# Res.net
KiCad netlist of a schematic drawn in Altium Designer
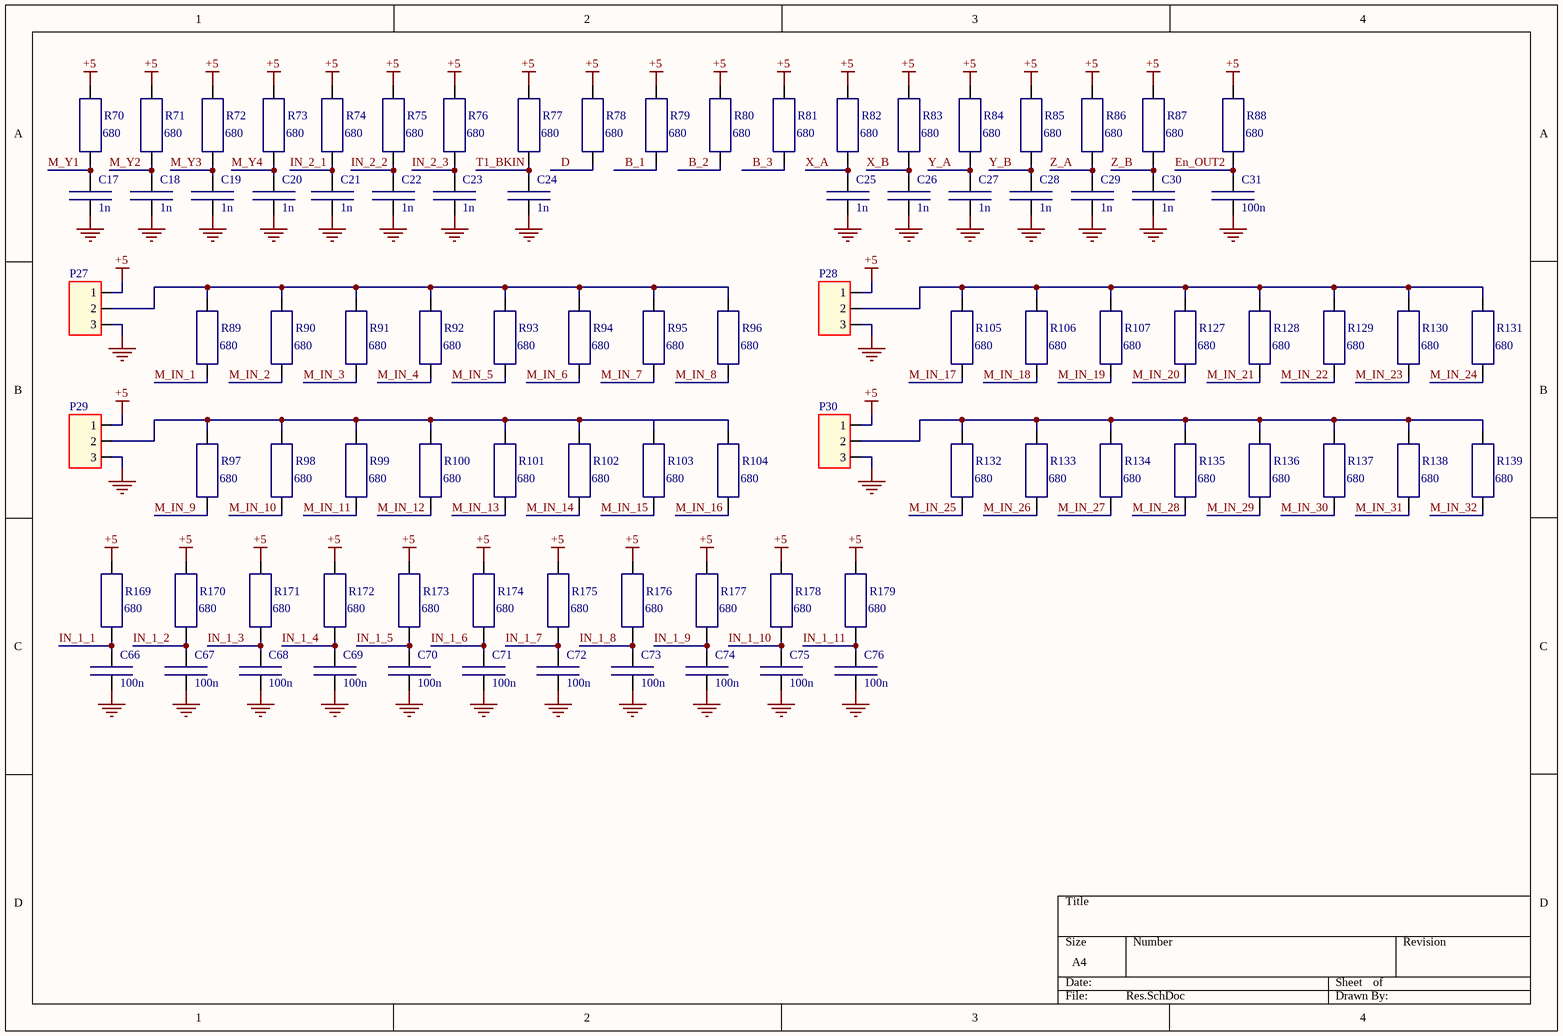
[diagram p0: Res.SchDoc]

(export (version "E")
  (design (tool "Eeschema 10.0.6"))
  (components
    (comp (ref "C17") (value "1n") (footprint "C0805") (libsource (lib "Library") (part "C0805")))
    (comp (ref "C18") (value "1n") (footprint "C0805") (libsource (lib "Library") (part "C0805")))
    (comp (ref "C19") (value "1n") (footprint "C0805") (libsource (lib "Library") (part "C0805")))
    (comp (ref "C20") (value "1n") (footprint "C0805") (libsource (lib "Library") (part "C0805")))
    (comp (ref "C21") (value "1n") (footprint "C0805") (libsource (lib "Library") (part "C0805")))
    (comp (ref "C22") (value "1n") (footprint "C0805") (libsource (lib "Library") (part "C0805")))
    (comp (ref "C23") (value "1n") (footprint "C0805") (libsource (lib "Library") (part "C0805")))
    (comp (ref "C24") (value "1n") (footprint "C0805") (libsource (lib "Library") (part "C0805")))
    (comp (ref "C25") (value "1n") (footprint "C0805") (libsource (lib "Library") (part "C0805")))
    (comp (ref "C26") (value "1n") (footprint "C0805") (libsource (lib "Library") (part "C0805")))
    (comp (ref "C27") (value "1n") (footprint "C0805") (libsource (lib "Library") (part "C0805")))
    (comp (ref "C28") (value "1n") (footprint "C0805") (libsource (lib "Library") (part "C0805")))
    (comp (ref "C29") (value "1n") (footprint "C0805") (libsource (lib "Library") (part "C0805")))
    (comp (ref "C30") (value "1n") (footprint "C0805") (libsource (lib "Library") (part "C0805")))
    (comp (ref "C31") (value "100n") (footprint "C0805") (libsource (lib "Library") (part "C0805")))
    (comp (ref "C66") (value "100n") (footprint "C0805") (libsource (lib "Library") (part "C0805")))
    (comp (ref "C67") (value "100n") (footprint "C0805") (libsource (lib "Library") (part "C0805")))
    (comp (ref "C68") (value "100n") (footprint "C0805") (libsource (lib "Library") (part "C0805")))
    (comp (ref "C69") (value "100n") (footprint "C0805") (libsource (lib "Library") (part "C0805")))
    (comp (ref "C70") (value "100n") (footprint "C0805") (libsource (lib "Library") (part "C0805")))
    (comp (ref "C71") (value "100n") (footprint "C0805") (libsource (lib "Library") (part "C0805")))
    (comp (ref "C72") (value "100n") (footprint "C0805") (libsource (lib "Library") (part "C0805")))
    (comp (ref "C73") (value "100n") (footprint "C0805") (libsource (lib "Library") (part "C0805")))
    (comp (ref "C74") (value "100n") (footprint "C0805") (libsource (lib "Library") (part "C0805")))
    (comp (ref "C75") (value "100n") (footprint "C0805") (libsource (lib "Library") (part "C0805")))
    (comp (ref "C76") (value "100n") (footprint "C0805") (libsource (lib "Library") (part "C0805")))
    (comp (ref "P27") (value "Con_3") (footprint "CON_3") (libsource (lib "Library") (part "Con_3")))
    (comp (ref "P28") (value "Con_3") (footprint "CON_3") (libsource (lib "Library") (part "Con_3")))
    (comp (ref "P29") (value "Con_3") (footprint "CON_3") (libsource (lib "Library") (part "Con_3")))
    (comp (ref "P30") (value "Con_3") (footprint "CON_3") (libsource (lib "Library") (part "Con_3")))
    (comp (ref "R70") (value "680") (footprint "R0805") (libsource (lib "Library") (part "R0805")))
    (comp (ref "R71") (value "680") (footprint "R0805") (libsource (lib "Library") (part "R0805")))
    (comp (ref "R72") (value "680") (footprint "R0805") (libsource (lib "Library") (part "R0805")))
    (comp (ref "R73") (value "680") (footprint "R0805") (libsource (lib "Library") (part "R0805")))
    (comp (ref "R74") (value "680") (footprint "R0805") (libsource (lib "Library") (part "R0805")))
    (comp (ref "R75") (value "680") (footprint "R0805") (libsource (lib "Library") (part "R0805")))
    (comp (ref "R76") (value "680") (footprint "R0805") (libsource (lib "Library") (part "R0805")))
    (comp (ref "R77") (value "680") (footprint "R0805") (libsource (lib "Library") (part "R0805")))
    (comp (ref "R78") (value "680") (footprint "R0805") (libsource (lib "Library") (part "R0805")))
    (comp (ref "R79") (value "680") (footprint "R0805") (libsource (lib "Library") (part "R0805")))
    (comp (ref "R80") (value "680") (footprint "R0805") (libsource (lib "Library") (part "R0805")))
    (comp (ref "R81") (value "680") (footprint "R0805") (libsource (lib "Library") (part "R0805")))
    (comp (ref "R82") (value "680") (footprint "R0805") (libsource (lib "Library") (part "R0805")))
    (comp (ref "R83") (value "680") (footprint "R0805") (libsource (lib "Library") (part "R0805")))
    (comp (ref "R84") (value "680") (footprint "R0805") (libsource (lib "Library") (part "R0805")))
    (comp (ref "R85") (value "680") (footprint "R0805") (libsource (lib "Library") (part "R0805")))
    (comp (ref "R86") (value "680") (footprint "R0805") (libsource (lib "Library") (part "R0805")))
    (comp (ref "R87") (value "680") (footprint "R0805") (libsource (lib "Library") (part "R0805")))
    (comp (ref "R88") (value "680") (footprint "R0805") (libsource (lib "Library") (part "R0805")))
    (comp (ref "R89") (value "680") (footprint "R0805") (libsource (lib "Library") (part "R0805")))
    (comp (ref "R90") (value "680") (footprint "R0805") (libsource (lib "Library") (part "R0805")))
    (comp (ref "R91") (value "680") (footprint "R0805") (libsource (lib "Library") (part "R0805")))
    (comp (ref "R92") (value "680") (footprint "R0805") (libsource (lib "Library") (part "R0805")))
    (comp (ref "R93") (value "680") (footprint "R0805") (libsource (lib "Library") (part "R0805")))
    (comp (ref "R94") (value "680") (footprint "R0805") (libsource (lib "Library") (part "R0805")))
    (comp (ref "R95") (value "680") (footprint "R0805") (libsource (lib "Library") (part "R0805")))
    (comp (ref "R96") (value "680") (footprint "R0805") (libsource (lib "Library") (part "R0805")))
    (comp (ref "R97") (value "680") (footprint "R0805") (libsource (lib "Library") (part "R0805")))
    (comp (ref "R98") (value "680") (footprint "R0805") (libsource (lib "Library") (part "R0805")))
    (comp (ref "R99") (value "680") (footprint "R0805") (libsource (lib "Library") (part "R0805")))
    (comp (ref "R100") (value "680") (footprint "R0805") (libsource (lib "Library") (part "R0805")))
    (comp (ref "R101") (value "680") (footprint "R0805") (libsource (lib "Library") (part "R0805")))
    (comp (ref "R102") (value "680") (footprint "R0805") (libsource (lib "Library") (part "R0805")))
    (comp (ref "R103") (value "680") (footprint "R0805") (libsource (lib "Library") (part "R0805")))
    (comp (ref "R104") (value "680") (footprint "R0805") (libsource (lib "Library") (part "R0805")))
    (comp (ref "R105") (value "680") (footprint "R0805") (libsource (lib "Library") (part "R0805")))
    (comp (ref "R106") (value "680") (footprint "R0805") (libsource (lib "Library") (part "R0805")))
    (comp (ref "R107") (value "680") (footprint "R0805") (libsource (lib "Library") (part "R0805")))
    (comp (ref "R127") (value "680") (footprint "R0805") (libsource (lib "Library") (part "R0805")))
    (comp (ref "R128") (value "680") (footprint "R0805") (libsource (lib "Library") (part "R0805")))
    (comp (ref "R129") (value "680") (footprint "R0805") (libsource (lib "Library") (part "R0805")))
    (comp (ref "R130") (value "680") (footprint "R0805") (libsource (lib "Library") (part "R0805")))
    (comp (ref "R131") (value "680") (footprint "R0805") (libsource (lib "Library") (part "R0805")))
    (comp (ref "R132") (value "680") (footprint "R0805") (libsource (lib "Library") (part "R0805")))
    (comp (ref "R133") (value "680") (footprint "R0805") (libsource (lib "Library") (part "R0805")))
    (comp (ref "R134") (value "680") (footprint "R0805") (libsource (lib "Library") (part "R0805")))
    (comp (ref "R135") (value "680") (footprint "R0805") (libsource (lib "Library") (part "R0805")))
    (comp (ref "R136") (value "680") (footprint "R0805") (libsource (lib "Library") (part "R0805")))
    (comp (ref "R137") (value "680") (footprint "R0805") (libsource (lib "Library") (part "R0805")))
    (comp (ref "R138") (value "680") (footprint "R0805") (libsource (lib "Library") (part "R0805")))
    (comp (ref "R139") (value "680") (footprint "R0805") (libsource (lib "Library") (part "R0805")))
    (comp (ref "R169") (value "680") (footprint "R0805") (libsource (lib "Library") (part "R0805")))
    (comp (ref "R170") (value "680") (footprint "R0805") (libsource (lib "Library") (part "R0805")))
    (comp (ref "R171") (value "680") (footprint "R0805") (libsource (lib "Library") (part "R0805")))
    (comp (ref "R172") (value "680") (footprint "R0805") (libsource (lib "Library") (part "R0805")))
    (comp (ref "R173") (value "680") (footprint "R0805") (libsource (lib "Library") (part "R0805")))
    (comp (ref "R174") (value "680") (footprint "R0805") (libsource (lib "Library") (part "R0805")))
    (comp (ref "R175") (value "680") (footprint "R0805") (libsource (lib "Library") (part "R0805")))
    (comp (ref "R176") (value "680") (footprint "R0805") (libsource (lib "Library") (part "R0805")))
    (comp (ref "R177") (value "680") (footprint "R0805") (libsource (lib "Library") (part "R0805")))
    (comp (ref "R178") (value "680") (footprint "R0805") (libsource (lib "Library") (part "R0805")))
    (comp (ref "R179") (value "680") (footprint "R0805") (libsource (lib "Library") (part "R0805")))
  )
  (nets
    (net (code "1") (name "+5") (class "Default")
      (node (ref "P27") (pin "1") (pinfunction "1_1") (pintype "passive"))
      (node (ref "P28") (pin "1") (pinfunction "1_1") (pintype "passive"))
      (node (ref "P29") (pin "1") (pinfunction "1_1") (pintype "passive"))
      (node (ref "P30") (pin "1") (pinfunction "1_1") (pintype "passive"))
      (node (ref "R169") (pin "2") (pinfunction "2_2") (pintype "passive"))
      (node (ref "R170") (pin "2") (pinfunction "2_2") (pintype "passive"))
      (node (ref "R171") (pin "2") (pinfunction "2_2") (pintype "passive"))
      (node (ref "R172") (pin "2") (pinfunction "2_2") (pintype "passive"))
      (node (ref "R173") (pin "2") (pinfunction "2_2") (pintype "passive"))
      (node (ref "R174") (pin "2") (pinfunction "2_2") (pintype "passive"))
      (node (ref "R175") (pin "2") (pinfunction "2_2") (pintype "passive"))
      (node (ref "R176") (pin "2") (pinfunction "2_2") (pintype "passive"))
      (node (ref "R177") (pin "2") (pinfunction "2_2") (pintype "passive"))
      (node (ref "R178") (pin "2") (pinfunction "2_2") (pintype "passive"))
      (node (ref "R179") (pin "2") (pinfunction "2_2") (pintype "passive"))
      (node (ref "R70") (pin "2") (pinfunction "2_2") (pintype "passive"))
      (node (ref "R71") (pin "2") (pinfunction "2_2") (pintype "passive"))
      (node (ref "R72") (pin "2") (pinfunction "2_2") (pintype "passive"))
      (node (ref "R73") (pin "2") (pinfunction "2_2") (pintype "passive"))
      (node (ref "R74") (pin "2") (pinfunction "2_2") (pintype "passive"))
      (node (ref "R75") (pin "2") (pinfunction "2_2") (pintype "passive"))
      (node (ref "R76") (pin "2") (pinfunction "2_2") (pintype "passive"))
      (node (ref "R77") (pin "2") (pinfunction "2_2") (pintype "passive"))
      (node (ref "R78") (pin "2") (pinfunction "2_2") (pintype "passive"))
      (node (ref "R79") (pin "2") (pinfunction "2_2") (pintype "passive"))
      (node (ref "R80") (pin "2") (pinfunction "2_2") (pintype "passive"))
      (node (ref "R81") (pin "2") (pinfunction "2_2") (pintype "passive"))
      (node (ref "R82") (pin "2") (pinfunction "2_2") (pintype "passive"))
      (node (ref "R83") (pin "2") (pinfunction "2_2") (pintype "passive"))
      (node (ref "R84") (pin "2") (pinfunction "2_2") (pintype "passive"))
      (node (ref "R85") (pin "2") (pinfunction "2_2") (pintype "passive"))
      (node (ref "R86") (pin "2") (pinfunction "2_2") (pintype "passive"))
      (node (ref "R87") (pin "2") (pinfunction "2_2") (pintype "passive"))
      (node (ref "R88") (pin "2") (pinfunction "2_2") (pintype "passive"))
    )
    (net (code "2") (name "/B_1") (class "Default")
      (node (ref "R79") (pin "1") (pinfunction "1_1") (pintype "passive"))
    )
    (net (code "3") (name "/B_2") (class "Default")
      (node (ref "R80") (pin "1") (pinfunction "1_1") (pintype "passive"))
    )
    (net (code "4") (name "/B_3") (class "Default")
      (node (ref "R81") (pin "1") (pinfunction "1_1") (pintype "passive"))
    )
    (net (code "5") (name "/D") (class "Default")
      (node (ref "R78") (pin "1") (pinfunction "1_1") (pintype "passive"))
    )
    (net (code "6") (name "/En_OUT2") (class "Default")
      (node (ref "C31") (pin "1") (pinfunction "1_1") (pintype "passive"))
      (node (ref "R88") (pin "1") (pinfunction "1_1") (pintype "passive"))
    )
    (net (code "7") (name "/IN_1_1") (class "Default")
      (node (ref "C66") (pin "1") (pinfunction "1_1") (pintype "passive"))
      (node (ref "R169") (pin "1") (pinfunction "1_1") (pintype "passive"))
    )
    (net (code "8") (name "/IN_1_2") (class "Default")
      (node (ref "C67") (pin "1") (pinfunction "1_1") (pintype "passive"))
      (node (ref "R170") (pin "1") (pinfunction "1_1") (pintype "passive"))
    )
    (net (code "9") (name "/IN_1_3") (class "Default")
      (node (ref "C68") (pin "1") (pinfunction "1_1") (pintype "passive"))
      (node (ref "R171") (pin "1") (pinfunction "1_1") (pintype "passive"))
    )
    (net (code "10") (name "/IN_1_4") (class "Default")
      (node (ref "C69") (pin "1") (pinfunction "1_1") (pintype "passive"))
      (node (ref "R172") (pin "1") (pinfunction "1_1") (pintype "passive"))
    )
    (net (code "11") (name "/IN_1_5") (class "Default")
      (node (ref "C70") (pin "1") (pinfunction "1_1") (pintype "passive"))
      (node (ref "R173") (pin "1") (pinfunction "1_1") (pintype "passive"))
    )
    (net (code "12") (name "/IN_1_6") (class "Default")
      (node (ref "C71") (pin "1") (pinfunction "1_1") (pintype "passive"))
      (node (ref "R174") (pin "1") (pinfunction "1_1") (pintype "passive"))
    )
    (net (code "13") (name "/IN_1_7") (class "Default")
      (node (ref "C72") (pin "1") (pinfunction "1_1") (pintype "passive"))
      (node (ref "R175") (pin "1") (pinfunction "1_1") (pintype "passive"))
    )
    (net (code "14") (name "/IN_1_8") (class "Default")
      (node (ref "C73") (pin "1") (pinfunction "1_1") (pintype "passive"))
      (node (ref "R176") (pin "1") (pinfunction "1_1") (pintype "passive"))
    )
    (net (code "15") (name "/IN_1_9") (class "Default")
      (node (ref "C74") (pin "1") (pinfunction "1_1") (pintype "passive"))
      (node (ref "R177") (pin "1") (pinfunction "1_1") (pintype "passive"))
    )
    (net (code "16") (name "/IN_1_10") (class "Default")
      (node (ref "C75") (pin "1") (pinfunction "1_1") (pintype "passive"))
      (node (ref "R178") (pin "1") (pinfunction "1_1") (pintype "passive"))
    )
    (net (code "17") (name "/IN_1_11") (class "Default")
      (node (ref "C76") (pin "1") (pinfunction "1_1") (pintype "passive"))
      (node (ref "R179") (pin "1") (pinfunction "1_1") (pintype "passive"))
    )
    (net (code "18") (name "/IN_2_1") (class "Default")
      (node (ref "C21") (pin "1") (pinfunction "1_1") (pintype "passive"))
      (node (ref "R74") (pin "1") (pinfunction "1_1") (pintype "passive"))
    )
    (net (code "19") (name "/IN_2_2") (class "Default")
      (node (ref "C22") (pin "1") (pinfunction "1_1") (pintype "passive"))
      (node (ref "R75") (pin "1") (pinfunction "1_1") (pintype "passive"))
    )
    (net (code "20") (name "/IN_2_3") (class "Default")
      (node (ref "C23") (pin "1") (pinfunction "1_1") (pintype "passive"))
      (node (ref "R76") (pin "1") (pinfunction "1_1") (pintype "passive"))
    )
    (net (code "21") (name "/M_IN_1") (class "Default")
      (node (ref "R89") (pin "1") (pinfunction "1_1") (pintype "passive"))
    )
    (net (code "22") (name "/M_IN_2") (class "Default")
      (node (ref "R90") (pin "1") (pinfunction "1_1") (pintype "passive"))
    )
    (net (code "23") (name "/M_IN_3") (class "Default")
      (node (ref "R91") (pin "1") (pinfunction "1_1") (pintype "passive"))
    )
    (net (code "24") (name "/M_IN_4") (class "Default")
      (node (ref "R92") (pin "1") (pinfunction "1_1") (pintype "passive"))
    )
    (net (code "25") (name "/M_IN_5") (class "Default")
      (node (ref "R93") (pin "1") (pinfunction "1_1") (pintype "passive"))
    )
    (net (code "26") (name "/M_IN_6") (class "Default")
      (node (ref "R94") (pin "1") (pinfunction "1_1") (pintype "passive"))
    )
    (net (code "27") (name "/M_IN_7") (class "Default")
      (node (ref "R95") (pin "1") (pinfunction "1_1") (pintype "passive"))
    )
    (net (code "28") (name "/M_IN_8") (class "Default")
      (node (ref "R96") (pin "1") (pinfunction "1_1") (pintype "passive"))
    )
    (net (code "29") (name "/M_IN_9") (class "Default")
      (node (ref "R97") (pin "1") (pinfunction "1_1") (pintype "passive"))
    )
    (net (code "30") (name "/M_IN_10") (class "Default")
      (node (ref "R98") (pin "1") (pinfunction "1_1") (pintype "passive"))
    )
    (net (code "31") (name "/M_IN_11") (class "Default")
      (node (ref "R99") (pin "1") (pinfunction "1_1") (pintype "passive"))
    )
    (net (code "32") (name "/M_IN_12") (class "Default")
      (node (ref "R100") (pin "1") (pinfunction "1_1") (pintype "passive"))
    )
    (net (code "33") (name "/M_IN_13") (class "Default")
      (node (ref "R101") (pin "1") (pinfunction "1_1") (pintype "passive"))
    )
    (net (code "34") (name "/M_IN_14") (class "Default")
      (node (ref "R102") (pin "1") (pinfunction "1_1") (pintype "passive"))
    )
    (net (code "35") (name "/M_IN_15") (class "Default")
      (node (ref "R103") (pin "1") (pinfunction "1_1") (pintype "passive"))
    )
    (net (code "36") (name "/M_IN_16") (class "Default")
      (node (ref "R104") (pin "1") (pinfunction "1_1") (pintype "passive"))
    )
    (net (code "37") (name "/M_IN_17") (class "Default")
      (node (ref "R105") (pin "1") (pinfunction "1_1") (pintype "passive"))
    )
    (net (code "38") (name "/M_IN_18") (class "Default")
      (node (ref "R106") (pin "1") (pinfunction "1_1") (pintype "passive"))
    )
    (net (code "39") (name "/M_IN_19") (class "Default")
      (node (ref "R107") (pin "1") (pinfunction "1_1") (pintype "passive"))
    )
    (net (code "40") (name "/M_IN_20") (class "Default")
      (node (ref "R127") (pin "1") (pinfunction "1_1") (pintype "passive"))
    )
    (net (code "41") (name "/M_IN_21") (class "Default")
      (node (ref "R128") (pin "1") (pinfunction "1_1") (pintype "passive"))
    )
    (net (code "42") (name "/M_IN_22") (class "Default")
      (node (ref "R129") (pin "1") (pinfunction "1_1") (pintype "passive"))
    )
    (net (code "43") (name "/M_IN_23") (class "Default")
      (node (ref "R130") (pin "1") (pinfunction "1_1") (pintype "passive"))
    )
    (net (code "44") (name "/M_IN_24") (class "Default")
      (node (ref "R131") (pin "1") (pinfunction "1_1") (pintype "passive"))
    )
    (net (code "45") (name "/M_IN_25") (class "Default")
      (node (ref "R132") (pin "1") (pinfunction "1_1") (pintype "passive"))
    )
    (net (code "46") (name "/M_IN_26") (class "Default")
      (node (ref "R133") (pin "1") (pinfunction "1_1") (pintype "passive"))
    )
    (net (code "47") (name "/M_IN_27") (class "Default")
      (node (ref "R134") (pin "1") (pinfunction "1_1") (pintype "passive"))
    )
    (net (code "48") (name "/M_IN_28") (class "Default")
      (node (ref "R135") (pin "1") (pinfunction "1_1") (pintype "passive"))
    )
    (net (code "49") (name "/M_IN_29") (class "Default")
      (node (ref "R136") (pin "1") (pinfunction "1_1") (pintype "passive"))
    )
    (net (code "50") (name "/M_IN_30") (class "Default")
      (node (ref "R137") (pin "1") (pinfunction "1_1") (pintype "passive"))
    )
    (net (code "51") (name "/M_IN_31") (class "Default")
      (node (ref "R138") (pin "1") (pinfunction "1_1") (pintype "passive"))
    )
    (net (code "52") (name "/M_IN_32") (class "Default")
      (node (ref "R139") (pin "1") (pinfunction "1_1") (pintype "passive"))
    )
    (net (code "53") (name "/M_Y1") (class "Default")
      (node (ref "C17") (pin "1") (pinfunction "1_1") (pintype "passive"))
      (node (ref "R70") (pin "1") (pinfunction "1_1") (pintype "passive"))
    )
    (net (code "54") (name "/M_Y2") (class "Default")
      (node (ref "C18") (pin "1") (pinfunction "1_1") (pintype "passive"))
      (node (ref "R71") (pin "1") (pinfunction "1_1") (pintype "passive"))
    )
    (net (code "55") (name "/M_Y3") (class "Default")
      (node (ref "C19") (pin "1") (pinfunction "1_1") (pintype "passive"))
      (node (ref "R72") (pin "1") (pinfunction "1_1") (pintype "passive"))
    )
    (net (code "56") (name "/M_Y4") (class "Default")
      (node (ref "C20") (pin "1") (pinfunction "1_1") (pintype "passive"))
      (node (ref "R73") (pin "1") (pinfunction "1_1") (pintype "passive"))
    )
    (net (code "57") (name "/T1_BKIN") (class "Default")
      (node (ref "C24") (pin "1") (pinfunction "1_1") (pintype "passive"))
      (node (ref "R77") (pin "1") (pinfunction "1_1") (pintype "passive"))
    )
    (net (code "58") (name "/X_A") (class "Default")
      (node (ref "C25") (pin "1") (pinfunction "1_1") (pintype "passive"))
      (node (ref "R82") (pin "1") (pinfunction "1_1") (pintype "passive"))
    )
    (net (code "59") (name "/X_B") (class "Default")
      (node (ref "C26") (pin "1") (pinfunction "1_1") (pintype "passive"))
      (node (ref "R83") (pin "1") (pinfunction "1_1") (pintype "passive"))
    )
    (net (code "60") (name "/Y_A") (class "Default")
      (node (ref "C27") (pin "1") (pinfunction "1_1") (pintype "passive"))
      (node (ref "R84") (pin "1") (pinfunction "1_1") (pintype "passive"))
    )
    (net (code "61") (name "/Y_B") (class "Default")
      (node (ref "C28") (pin "1") (pinfunction "1_1") (pintype "passive"))
      (node (ref "R85") (pin "1") (pinfunction "1_1") (pintype "passive"))
    )
    (net (code "62") (name "/Z_A") (class "Default")
      (node (ref "C29") (pin "1") (pinfunction "1_1") (pintype "passive"))
      (node (ref "R86") (pin "1") (pinfunction "1_1") (pintype "passive"))
    )
    (net (code "63") (name "/Z_B") (class "Default")
      (node (ref "C30") (pin "1") (pinfunction "1_1") (pintype "passive"))
      (node (ref "R87") (pin "1") (pinfunction "1_1") (pintype "passive"))
    )
    (net (code "64") (name "GND") (class "Default")
      (node (ref "C17") (pin "2") (pinfunction "2_2") (pintype "passive"))
      (node (ref "C18") (pin "2") (pinfunction "2_2") (pintype "passive"))
      (node (ref "C19") (pin "2") (pinfunction "2_2") (pintype "passive"))
      (node (ref "C20") (pin "2") (pinfunction "2_2") (pintype "passive"))
      (node (ref "C21") (pin "2") (pinfunction "2_2") (pintype "passive"))
      (node (ref "C22") (pin "2") (pinfunction "2_2") (pintype "passive"))
      (node (ref "C23") (pin "2") (pinfunction "2_2") (pintype "passive"))
      (node (ref "C24") (pin "2") (pinfunction "2_2") (pintype "passive"))
      (node (ref "C25") (pin "2") (pinfunction "2_2") (pintype "passive"))
      (node (ref "C26") (pin "2") (pinfunction "2_2") (pintype "passive"))
      (node (ref "C27") (pin "2") (pinfunction "2_2") (pintype "passive"))
      (node (ref "C28") (pin "2") (pinfunction "2_2") (pintype "passive"))
      (node (ref "C29") (pin "2") (pinfunction "2_2") (pintype "passive"))
      (node (ref "C30") (pin "2") (pinfunction "2_2") (pintype "passive"))
      (node (ref "C31") (pin "2") (pinfunction "2_2") (pintype "passive"))
      (node (ref "C66") (pin "2") (pinfunction "2_2") (pintype "passive"))
      (node (ref "C67") (pin "2") (pinfunction "2_2") (pintype "passive"))
      (node (ref "C68") (pin "2") (pinfunction "2_2") (pintype "passive"))
      (node (ref "C69") (pin "2") (pinfunction "2_2") (pintype "passive"))
      (node (ref "C70") (pin "2") (pinfunction "2_2") (pintype "passive"))
      (node (ref "C71") (pin "2") (pinfunction "2_2") (pintype "passive"))
      (node (ref "C72") (pin "2") (pinfunction "2_2") (pintype "passive"))
      (node (ref "C73") (pin "2") (pinfunction "2_2") (pintype "passive"))
      (node (ref "C74") (pin "2") (pinfunction "2_2") (pintype "passive"))
      (node (ref "C75") (pin "2") (pinfunction "2_2") (pintype "passive"))
      (node (ref "C76") (pin "2") (pinfunction "2_2") (pintype "passive"))
      (node (ref "P27") (pin "3") (pinfunction "3_3") (pintype "passive"))
      (node (ref "P28") (pin "3") (pinfunction "3_3") (pintype "passive"))
      (node (ref "P29") (pin "3") (pinfunction "3_3") (pintype "passive"))
      (node (ref "P30") (pin "3") (pinfunction "3_3") (pintype "passive"))
    )
    (net (code "65") (name "Net-(P27-Pad2)") (class "Default")
      (node (ref "P27") (pin "2") (pinfunction "2_2") (pintype "passive"))
      (node (ref "R89") (pin "2") (pinfunction "2_2") (pintype "passive"))
      (node (ref "R90") (pin "2") (pinfunction "2_2") (pintype "passive"))
      (node (ref "R91") (pin "2") (pinfunction "2_2") (pintype "passive"))
      (node (ref "R92") (pin "2") (pinfunction "2_2") (pintype "passive"))
      (node (ref "R93") (pin "2") (pinfunction "2_2") (pintype "passive"))
      (node (ref "R94") (pin "2") (pinfunction "2_2") (pintype "passive"))
      (node (ref "R95") (pin "2") (pinfunction "2_2") (pintype "passive"))
      (node (ref "R96") (pin "2") (pinfunction "2_2") (pintype "passive"))
    )
    (net (code "66") (name "Net-(P28-Pad2)") (class "Default")
      (node (ref "P28") (pin "2") (pinfunction "2_2") (pintype "passive"))
      (node (ref "R105") (pin "2") (pinfunction "2_2") (pintype "passive"))
      (node (ref "R106") (pin "2") (pinfunction "2_2") (pintype "passive"))
      (node (ref "R107") (pin "2") (pinfunction "2_2") (pintype "passive"))
      (node (ref "R127") (pin "2") (pinfunction "2_2") (pintype "passive"))
      (node (ref "R128") (pin "2") (pinfunction "2_2") (pintype "passive"))
      (node (ref "R129") (pin "2") (pinfunction "2_2") (pintype "passive"))
      (node (ref "R130") (pin "2") (pinfunction "2_2") (pintype "passive"))
      (node (ref "R131") (pin "2") (pinfunction "2_2") (pintype "passive"))
    )
    (net (code "67") (name "Net-(P29-Pad2)") (class "Default")
      (node (ref "P29") (pin "2") (pinfunction "2_2") (pintype "passive"))
      (node (ref "R100") (pin "2") (pinfunction "2_2") (pintype "passive"))
      (node (ref "R101") (pin "2") (pinfunction "2_2") (pintype "passive"))
      (node (ref "R102") (pin "2") (pinfunction "2_2") (pintype "passive"))
      (node (ref "R103") (pin "2") (pinfunction "2_2") (pintype "passive"))
      (node (ref "R104") (pin "2") (pinfunction "2_2") (pintype "passive"))
      (node (ref "R97") (pin "2") (pinfunction "2_2") (pintype "passive"))
      (node (ref "R98") (pin "2") (pinfunction "2_2") (pintype "passive"))
      (node (ref "R99") (pin "2") (pinfunction "2_2") (pintype "passive"))
    )
    (net (code "68") (name "Net-(P30-Pad2)") (class "Default")
      (node (ref "P30") (pin "2") (pinfunction "2_2") (pintype "passive"))
      (node (ref "R132") (pin "2") (pinfunction "2_2") (pintype "passive"))
      (node (ref "R133") (pin "2") (pinfunction "2_2") (pintype "passive"))
      (node (ref "R134") (pin "2") (pinfunction "2_2") (pintype "passive"))
      (node (ref "R135") (pin "2") (pinfunction "2_2") (pintype "passive"))
      (node (ref "R136") (pin "2") (pinfunction "2_2") (pintype "passive"))
      (node (ref "R137") (pin "2") (pinfunction "2_2") (pintype "passive"))
      (node (ref "R138") (pin "2") (pinfunction "2_2") (pintype "passive"))
      (node (ref "R139") (pin "2") (pinfunction "2_2") (pintype "passive"))
    )
  )
)
